# BaseMachine_Exio_Load_Save.net
KiCad netlist of a schematic drawn in EAGLE
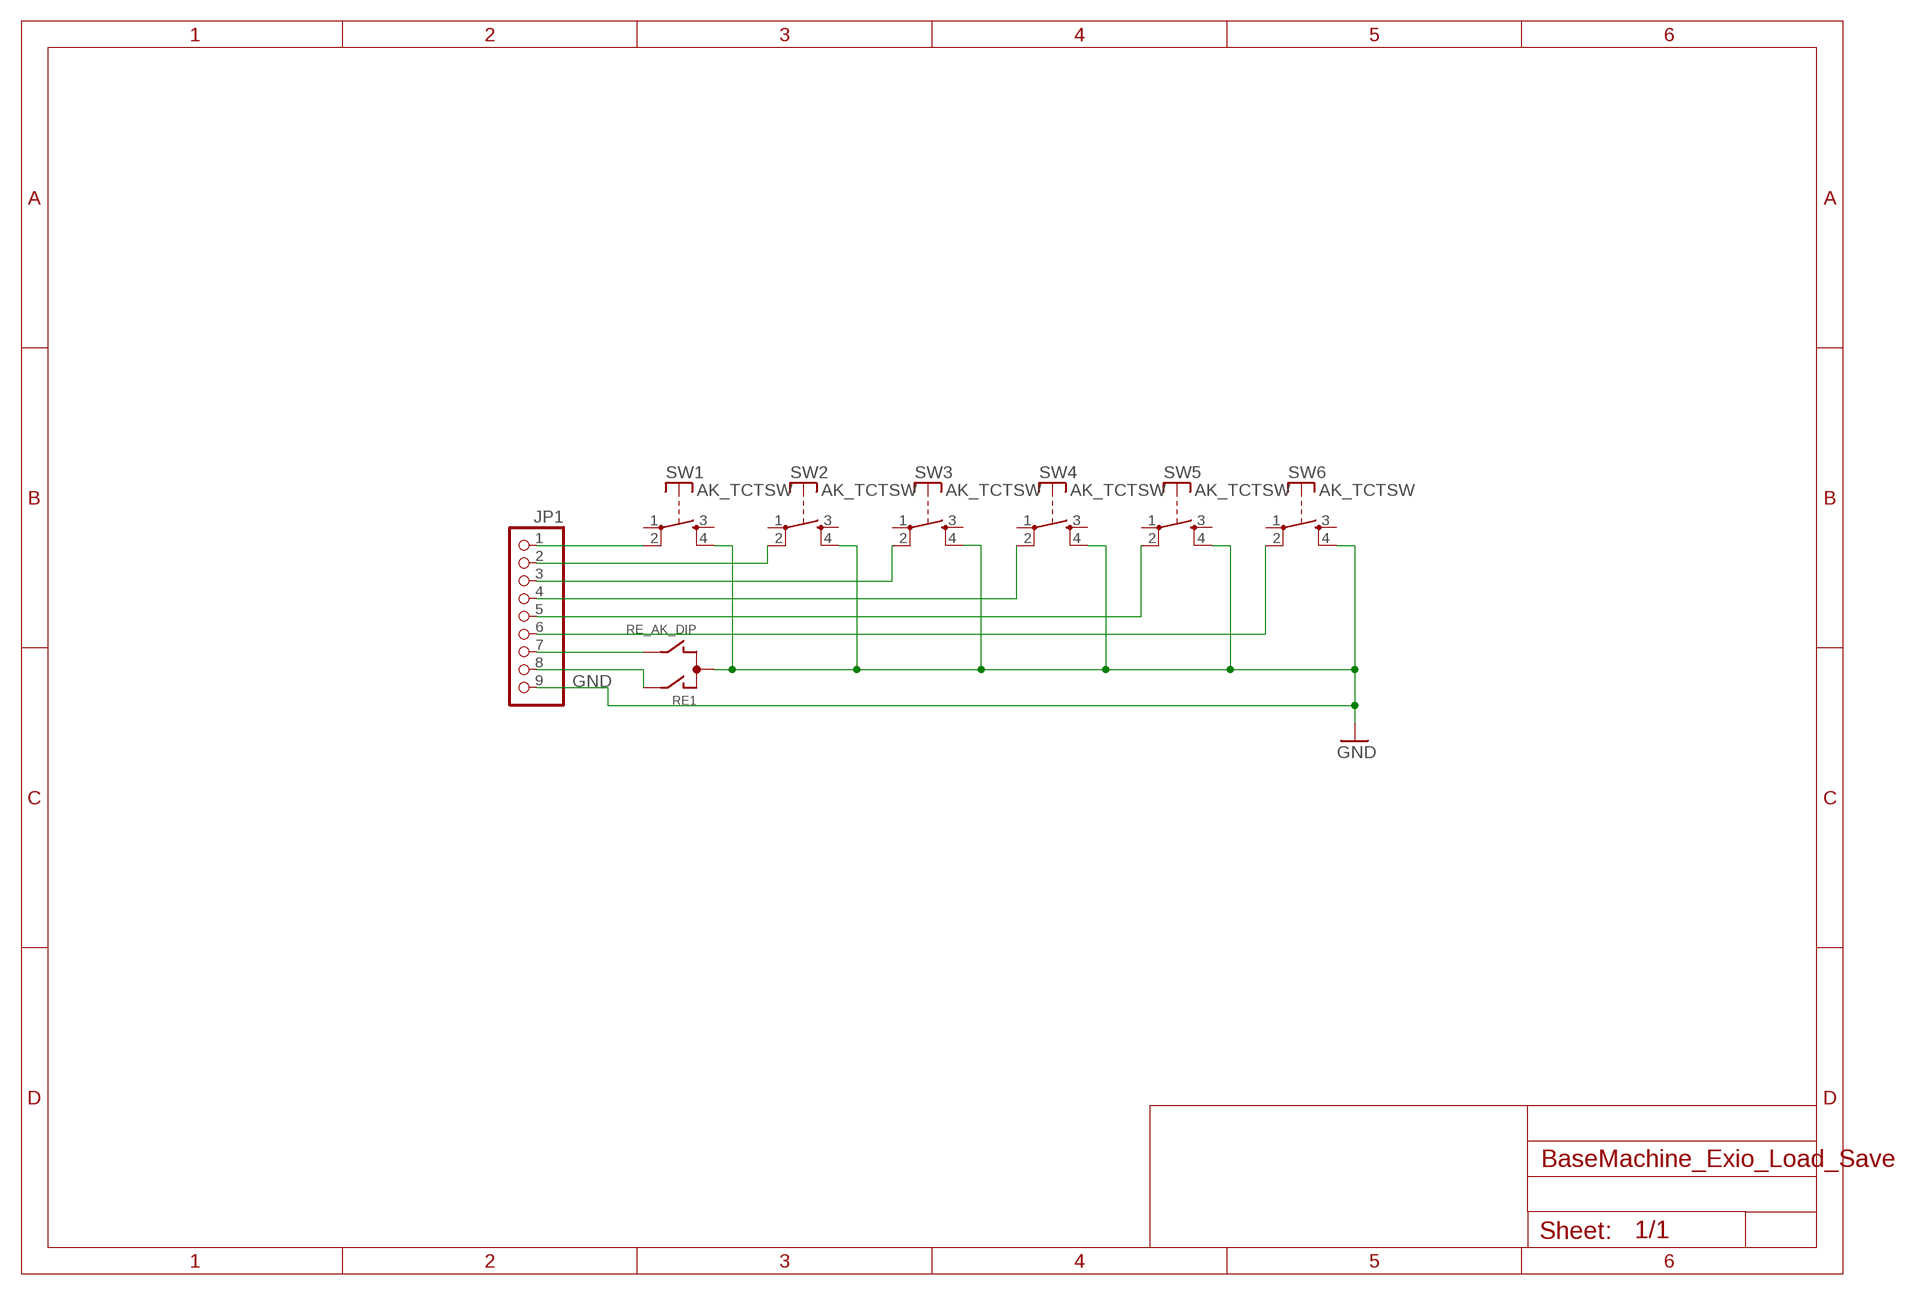
[diagram p0: schematic, sheet 1]

(export (version "E")
  (design (tool "Eeschema 10.0.6"))
  (components
    (comp (ref "JP1")
      (value "PINHD-1X9")
      (footprint "eagle-import:1X09")
      (libsource (lib "eagle-import") (part "PINHD-1X9"))
    )
    (comp (ref "RE1")
      (value "RE_AK_DIP")
      (footprint "eagle-import:RE_AK_DIP")
      (libsource (lib "eagle-import") (part "RE_AK_DIP"))
    )
    (comp (ref "SW1")
      (value "AK_TCTSW")
      (footprint "eagle-import:TME1")
      (libsource (lib "eagle-import") (part "AK_TCTSW"))
    )
    (comp (ref "SW2")
      (value "AK_TCTSW")
      (footprint "eagle-import:TME1")
      (libsource (lib "eagle-import") (part "AK_TCTSW"))
    )
    (comp (ref "SW3")
      (value "AK_TCTSW")
      (footprint "eagle-import:TME1")
      (libsource (lib "eagle-import") (part "AK_TCTSW"))
    )
    (comp (ref "SW4")
      (value "AK_TCTSW")
      (footprint "eagle-import:TME1")
      (libsource (lib "eagle-import") (part "AK_TCTSW"))
    )
    (comp (ref "SW5")
      (value "AK_TCTSW")
      (footprint "eagle-import:TME1")
      (libsource (lib "eagle-import") (part "AK_TCTSW"))
    )
    (comp (ref "SW6")
      (value "AK_TCTSW")
      (footprint "eagle-import:TME1")
      (libsource (lib "eagle-import") (part "AK_TCTSW"))
    )
  )
  (nets
    (net (code "1") (name "GND") (class "Default")
      (node (ref "JP1") (pin "9") (pinfunction "9_9") (pintype "passive"))
      (node (ref "RE1") (pin "P$3") (pinfunction "C_P$3") (pintype "passive"))
      (node (ref "SW1") (pin "4") (pinfunction "S_4") (pintype "passive"))
      (node (ref "SW2") (pin "4") (pinfunction "S_4") (pintype "passive"))
      (node (ref "SW3") (pin "4") (pinfunction "S_4") (pintype "passive"))
      (node (ref "SW4") (pin "4") (pinfunction "S_4") (pintype "passive"))
      (node (ref "SW5") (pin "4") (pinfunction "S_4") (pintype "passive"))
      (node (ref "SW6") (pin "4") (pinfunction "S_4") (pintype "passive"))
    )
    (net (code "2") (name "Net-(JP1-Pad1)") (class "Default")
      (node (ref "JP1") (pin "1") (pinfunction "1_1") (pintype "passive"))
      (node (ref "SW1") (pin "2") (pinfunction "P_2") (pintype "passive"))
    )
    (net (code "3") (name "Net-(JP1-Pad2)") (class "Default")
      (node (ref "JP1") (pin "2") (pinfunction "2_2") (pintype "passive"))
      (node (ref "SW2") (pin "2") (pinfunction "P_2") (pintype "passive"))
    )
    (net (code "4") (name "Net-(JP1-Pad3)") (class "Default")
      (node (ref "JP1") (pin "3") (pinfunction "3_3") (pintype "passive"))
      (node (ref "SW3") (pin "2") (pinfunction "P_2") (pintype "passive"))
    )
    (net (code "5") (name "Net-(JP1-Pad4)") (class "Default")
      (node (ref "JP1") (pin "4") (pinfunction "4_4") (pintype "passive"))
      (node (ref "SW4") (pin "2") (pinfunction "P_2") (pintype "passive"))
    )
    (net (code "6") (name "Net-(JP1-Pad5)") (class "Default")
      (node (ref "JP1") (pin "5") (pinfunction "5_5") (pintype "passive"))
      (node (ref "SW5") (pin "2") (pinfunction "P_2") (pintype "passive"))
    )
    (net (code "7") (name "Net-(JP1-Pad6)") (class "Default")
      (node (ref "JP1") (pin "6") (pinfunction "6_6") (pintype "passive"))
      (node (ref "SW6") (pin "2") (pinfunction "P_2") (pintype "passive"))
    )
    (net (code "8") (name "Net-(RE1-A)") (class "Default")
      (node (ref "JP1") (pin "8") (pinfunction "8_8") (pintype "passive"))
      (node (ref "RE1") (pin "P$2") (pinfunction "A_P$2") (pintype "passive"))
    )
    (net (code "9") (name "Net-(RE1-B)") (class "Default")
      (node (ref "JP1") (pin "7") (pinfunction "7_7") (pintype "passive"))
      (node (ref "RE1") (pin "P$4") (pinfunction "B_P$4") (pintype "passive"))
    )
    (net (code "10") (name "unconnected-(SW1-P-Pad1)") (class "Default")
      (node (ref "SW1") (pin "1") (pinfunction "P_1") (pintype "passive"))
    )
    (net (code "11") (name "unconnected-(SW1-S-Pad3)") (class "Default")
      (node (ref "SW1") (pin "3") (pinfunction "S_3") (pintype "passive"))
    )
    (net (code "12") (name "unconnected-(SW2-P-Pad1)") (class "Default")
      (node (ref "SW2") (pin "1") (pinfunction "P_1") (pintype "passive"))
    )
    (net (code "13") (name "unconnected-(SW2-S-Pad3)") (class "Default")
      (node (ref "SW2") (pin "3") (pinfunction "S_3") (pintype "passive"))
    )
    (net (code "14") (name "unconnected-(SW3-P-Pad1)") (class "Default")
      (node (ref "SW3") (pin "1") (pinfunction "P_1") (pintype "passive"))
    )
    (net (code "15") (name "unconnected-(SW3-S-Pad3)") (class "Default")
      (node (ref "SW3") (pin "3") (pinfunction "S_3") (pintype "passive"))
    )
    (net (code "16") (name "unconnected-(SW4-P-Pad1)") (class "Default")
      (node (ref "SW4") (pin "1") (pinfunction "P_1") (pintype "passive"))
    )
    (net (code "17") (name "unconnected-(SW4-S-Pad3)") (class "Default")
      (node (ref "SW4") (pin "3") (pinfunction "S_3") (pintype "passive"))
    )
    (net (code "18") (name "unconnected-(SW5-P-Pad1)") (class "Default")
      (node (ref "SW5") (pin "1") (pinfunction "P_1") (pintype "passive"))
    )
    (net (code "19") (name "unconnected-(SW5-S-Pad3)") (class "Default")
      (node (ref "SW5") (pin "3") (pinfunction "S_3") (pintype "passive"))
    )
    (net (code "20") (name "unconnected-(SW6-P-Pad1)") (class "Default")
      (node (ref "SW6") (pin "1") (pinfunction "P_1") (pintype "passive"))
    )
    (net (code "21") (name "unconnected-(SW6-S-Pad3)") (class "Default")
      (node (ref "SW6") (pin "3") (pinfunction "S_3") (pintype "passive"))
    )
  )
)
